# GSM_Communication_Signals.net
KiCad netlist of a schematic drawn in Altium Designer
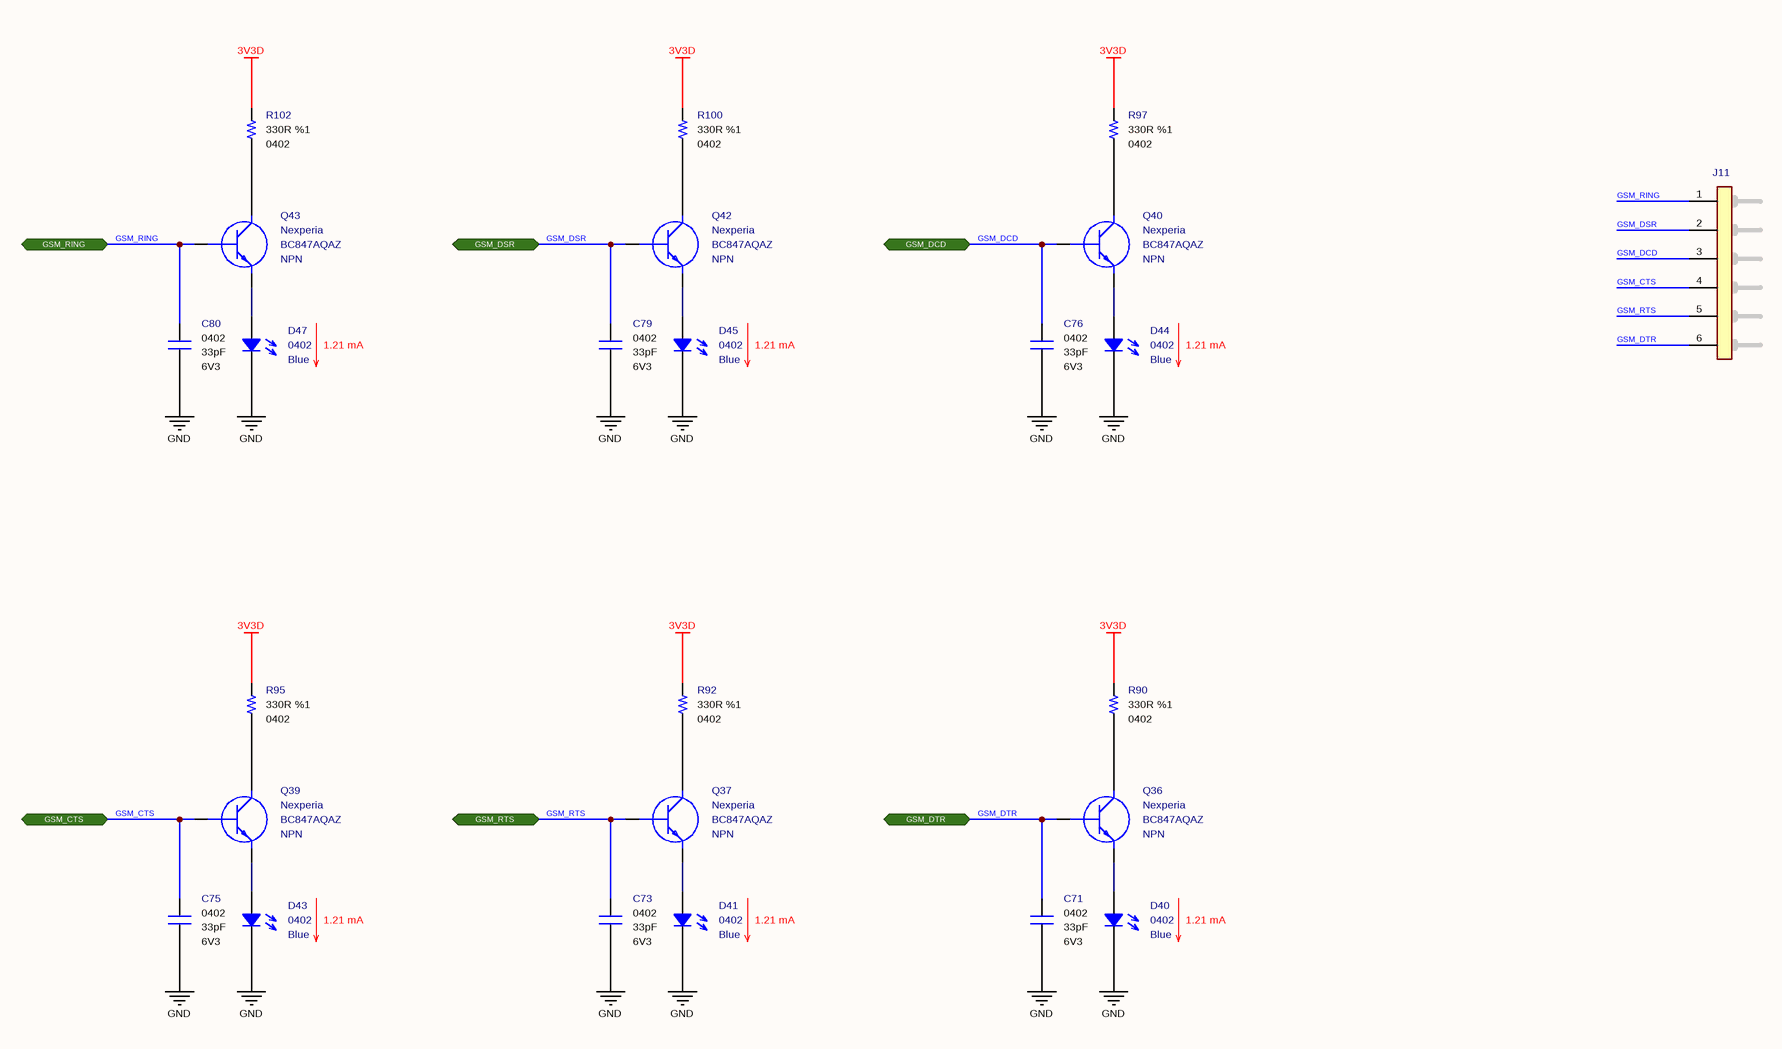
[diagram p0: GSM Communication Signals.SchDoc]

(export (version "E")
  (design (tool "Eeschema 10.0.6"))
  (components
    (comp (ref "C71")
      (value "33pF")
      (footprint "CAPACITOR_0402")
      (description "Capacitor - 33pF [0402] (Ceramic)")
      (fields
        (field (name "CASE") "0402")
        (field (name "TOLERANCE") "10%")
        (field (name "VOLTAGE") "6V3")
        (field (name "MANUFACTURER PART NUMBER") "C0402C330J9RACAUTO")
      )
      (libsource (lib "Ovoo_Library") (part "Capacitor - 33pF [0402-6V3]"))
    )
    (comp (ref "C73")
      (value "33pF")
      (footprint "CAPACITOR_0402")
      (description "Capacitor - 33pF [0402] (Ceramic)")
      (fields
        (field (name "CASE") "0402")
        (field (name "TOLERANCE") "10%")
        (field (name "VOLTAGE") "6V3")
        (field (name "MANUFACTURER PART NUMBER") "C0402C330J9RACAUTO")
      )
      (libsource (lib "Ovoo_Library") (part "Capacitor - 33pF [0402-6V3]"))
    )
    (comp (ref "C75")
      (value "33pF")
      (footprint "CAPACITOR_0402")
      (description "Capacitor - 33pF [0402] (Ceramic)")
      (fields
        (field (name "CASE") "0402")
        (field (name "TOLERANCE") "10%")
        (field (name "VOLTAGE") "6V3")
        (field (name "MANUFACTURER PART NUMBER") "C0402C330J9RACAUTO")
      )
      (libsource (lib "Ovoo_Library") (part "Capacitor - 33pF [0402-6V3]"))
    )
    (comp (ref "C76")
      (value "33pF")
      (footprint "CAPACITOR_0402")
      (description "Capacitor - 33pF [0402] (Ceramic)")
      (fields
        (field (name "CASE") "0402")
        (field (name "TOLERANCE") "10%")
        (field (name "VOLTAGE") "6V3")
        (field (name "MANUFACTURER PART NUMBER") "C0402C330J9RACAUTO")
      )
      (libsource (lib "Ovoo_Library") (part "Capacitor - 33pF [0402-6V3]"))
    )
    (comp (ref "C79")
      (value "33pF")
      (footprint "CAPACITOR_0402")
      (description "Capacitor - 33pF [0402] (Ceramic)")
      (fields
        (field (name "CASE") "0402")
        (field (name "TOLERANCE") "10%")
        (field (name "VOLTAGE") "6V3")
        (field (name "MANUFACTURER PART NUMBER") "C0402C330J9RACAUTO")
      )
      (libsource (lib "Ovoo_Library") (part "Capacitor - 33pF [0402-6V3]"))
    )
    (comp (ref "C80")
      (value "33pF")
      (footprint "CAPACITOR_0402")
      (description "Capacitor - 33pF [0402] (Ceramic)")
      (fields
        (field (name "CASE") "0402")
        (field (name "TOLERANCE") "10%")
        (field (name "VOLTAGE") "6V3")
        (field (name "MANUFACTURER PART NUMBER") "C0402C330J9RACAUTO")
      )
      (libsource (lib "Ovoo_Library") (part "Capacitor - 33pF [0402-6V3]"))
    )
    (comp (ref "D40")
      (value "SMD LED (Blue)")
      (footprint "LED_0402")
      (description "Standard LEDs - SMD PICOLEDTM;BLUE LED; 25M @ 5MA")
      (fields
        (field (name "MANUFACTURER_PART_NUMBER") "SMLP13BC8TT86")
        (field (name "MOUSER_PART_NUMBER") "755-SMLP13BC8TT86")
        (field (name "CASE") "0402")
        (field (name "COLOR") "Blue")
      )
      (libsource (lib "Ovoo_Library") (part "Diode - LED (0402-Blue)"))
    )
    (comp (ref "D41")
      (value "SMD LED (Blue)")
      (footprint "LED_0402")
      (description "Standard LEDs - SMD PICOLEDTM;BLUE LED; 25M @ 5MA")
      (fields
        (field (name "MANUFACTURER_PART_NUMBER") "SMLP13BC8TT86")
        (field (name "MOUSER_PART_NUMBER") "755-SMLP13BC8TT86")
        (field (name "CASE") "0402")
        (field (name "COLOR") "Blue")
      )
      (libsource (lib "Ovoo_Library") (part "Diode - LED (0402-Blue)"))
    )
    (comp (ref "D43")
      (value "SMD LED (Blue)")
      (footprint "LED_0402")
      (description "Standard LEDs - SMD PICOLEDTM;BLUE LED; 25M @ 5MA")
      (fields
        (field (name "MANUFACTURER_PART_NUMBER") "SMLP13BC8TT86")
        (field (name "MOUSER_PART_NUMBER") "755-SMLP13BC8TT86")
        (field (name "CASE") "0402")
        (field (name "COLOR") "Blue")
      )
      (libsource (lib "Ovoo_Library") (part "Diode - LED (0402-Blue)"))
    )
    (comp (ref "D44")
      (value "SMD LED (Blue)")
      (footprint "LED_0402")
      (description "Standard LEDs - SMD PICOLEDTM;BLUE LED; 25M @ 5MA")
      (fields
        (field (name "MANUFACTURER_PART_NUMBER") "SMLP13BC8TT86")
        (field (name "MOUSER_PART_NUMBER") "755-SMLP13BC8TT86")
        (field (name "CASE") "0402")
        (field (name "COLOR") "Blue")
      )
      (libsource (lib "Ovoo_Library") (part "Diode - LED (0402-Blue)"))
    )
    (comp (ref "D45")
      (value "SMD LED (Blue)")
      (footprint "LED_0402")
      (description "Standard LEDs - SMD PICOLEDTM;BLUE LED; 25M @ 5MA")
      (fields
        (field (name "MANUFACTURER_PART_NUMBER") "SMLP13BC8TT86")
        (field (name "MOUSER_PART_NUMBER") "755-SMLP13BC8TT86")
        (field (name "CASE") "0402")
        (field (name "COLOR") "Blue")
      )
      (libsource (lib "Ovoo_Library") (part "Diode - LED (0402-Blue)"))
    )
    (comp (ref "D47")
      (value "SMD LED (Blue)")
      (footprint "LED_0402")
      (description "Standard LEDs - SMD PICOLEDTM;BLUE LED; 25M @ 5MA")
      (fields
        (field (name "MANUFACTURER_PART_NUMBER") "SMLP13BC8TT86")
        (field (name "MOUSER_PART_NUMBER") "755-SMLP13BC8TT86")
        (field (name "CASE") "0402")
        (field (name "COLOR") "Blue")
      )
      (libsource (lib "Ovoo_Library") (part "Diode - LED (0402-Blue)"))
    )
    (comp (ref "J11")
      (value "2.54 mm Pitch 6P Male Connector")
      (footprint "6P Header")
      (description "Headers & Wire Housings BREAKAWAY HDR VERT 6")
      (fields
        (field (name "MANUFACTURER PART NUMBER") "22-28-4063")
        (field (name "MOUSER PART NUMBER") "538-22-28-4063")
      )
      (libsource (lib "Ovoo_Library") (part "Connector - Male Header 6P (2.54)"))
    )
    (comp (ref "Q36")
      (value "Bipolar NPN Transistors")
      (footprint "SOT1215")
      (description "Bipolar Transistors - BJT BC847AQA/DFN1010D-3/REEL 7\" Q2")
      (fields
        (field (name "MOUSER_PART_NUMBER") "771-BC847AQAZ")
        (field (name "MANUFACTURER_NAME") "Nexperia")
        (field (name "MANUFACTURER_PART_NUMBER") "BC847AQAZ")
        (field (name "POLARITY") "NPN")
      )
      (libsource (lib "Ovoo_Library") (part "Transistor - BC847"))
    )
    (comp (ref "Q37")
      (value "Bipolar NPN Transistors")
      (footprint "SOT1215")
      (description "Bipolar Transistors - BJT BC847AQA/DFN1010D-3/REEL 7\" Q2")
      (fields
        (field (name "MOUSER_PART_NUMBER") "771-BC847AQAZ")
        (field (name "MANUFACTURER_NAME") "Nexperia")
        (field (name "MANUFACTURER_PART_NUMBER") "BC847AQAZ")
        (field (name "POLARITY") "NPN")
      )
      (libsource (lib "Ovoo_Library") (part "Transistor - BC847"))
    )
    (comp (ref "Q39")
      (value "Bipolar NPN Transistors")
      (footprint "SOT1215")
      (description "Bipolar Transistors - BJT BC847AQA/DFN1010D-3/REEL 7\" Q2")
      (fields
        (field (name "MOUSER_PART_NUMBER") "771-BC847AQAZ")
        (field (name "MANUFACTURER_NAME") "Nexperia")
        (field (name "MANUFACTURER_PART_NUMBER") "BC847AQAZ")
        (field (name "POLARITY") "NPN")
      )
      (libsource (lib "Ovoo_Library") (part "Transistor - BC847"))
    )
    (comp (ref "Q40")
      (value "Bipolar NPN Transistors")
      (footprint "SOT1215")
      (description "Bipolar Transistors - BJT BC847AQA/DFN1010D-3/REEL 7\" Q2")
      (fields
        (field (name "MOUSER_PART_NUMBER") "771-BC847AQAZ")
        (field (name "MANUFACTURER_NAME") "Nexperia")
        (field (name "MANUFACTURER_PART_NUMBER") "BC847AQAZ")
        (field (name "POLARITY") "NPN")
      )
      (libsource (lib "Ovoo_Library") (part "Transistor - BC847"))
    )
    (comp (ref "Q42")
      (value "Bipolar NPN Transistors")
      (footprint "SOT1215")
      (description "Bipolar Transistors - BJT BC847AQA/DFN1010D-3/REEL 7\" Q2")
      (fields
        (field (name "MOUSER_PART_NUMBER") "771-BC847AQAZ")
        (field (name "MANUFACTURER_NAME") "Nexperia")
        (field (name "MANUFACTURER_PART_NUMBER") "BC847AQAZ")
        (field (name "POLARITY") "NPN")
      )
      (libsource (lib "Ovoo_Library") (part "Transistor - BC847"))
    )
    (comp (ref "Q43")
      (value "Bipolar NPN Transistors")
      (footprint "SOT1215")
      (description "Bipolar Transistors - BJT BC847AQA/DFN1010D-3/REEL 7\" Q2")
      (fields
        (field (name "MOUSER_PART_NUMBER") "771-BC847AQAZ")
        (field (name "MANUFACTURER_NAME") "Nexperia")
        (field (name "MANUFACTURER_PART_NUMBER") "BC847AQAZ")
        (field (name "POLARITY") "NPN")
      )
      (libsource (lib "Ovoo_Library") (part "Transistor - BC847"))
    )
    (comp (ref "R90")
      (value "330R")
      (footprint "RESISTOR_0402")
      (description "Thick Film Resistors - SMD 1/16 W 330 Ohm 1%")
      (fields
        (field (name "TOLERANCE") "%1")
        (field (name "CASE") "0402")
        (field (name "MANUFACTURER PART NUMBER") "CRCW0402330RFKED")
        (field (name "MOUSER PART NUMBER") "71-CRCW0402-330-E3")
      )
      (libsource (lib "Ovoo_Library") (part "Resistor - 330R"))
    )
    (comp (ref "R92")
      (value "330R")
      (footprint "RESISTOR_0402")
      (description "Thick Film Resistors - SMD 1/16 W 330 Ohm 1%")
      (fields
        (field (name "TOLERANCE") "%1")
        (field (name "CASE") "0402")
        (field (name "MANUFACTURER PART NUMBER") "CRCW0402330RFKED")
        (field (name "MOUSER PART NUMBER") "71-CRCW0402-330-E3")
      )
      (libsource (lib "Ovoo_Library") (part "Resistor - 330R"))
    )
    (comp (ref "R95")
      (value "330R")
      (footprint "RESISTOR_0402")
      (description "Thick Film Resistors - SMD 1/16 W 330 Ohm 1%")
      (fields
        (field (name "TOLERANCE") "%1")
        (field (name "CASE") "0402")
        (field (name "MANUFACTURER PART NUMBER") "CRCW0402330RFKED")
        (field (name "MOUSER PART NUMBER") "71-CRCW0402-330-E3")
      )
      (libsource (lib "Ovoo_Library") (part "Resistor - 330R"))
    )
    (comp (ref "R97")
      (value "330R")
      (footprint "RESISTOR_0402")
      (description "Thick Film Resistors - SMD 1/16 W 330 Ohm 1%")
      (fields
        (field (name "TOLERANCE") "%1")
        (field (name "CASE") "0402")
        (field (name "MANUFACTURER PART NUMBER") "CRCW0402330RFKED")
        (field (name "MOUSER PART NUMBER") "71-CRCW0402-330-E3")
      )
      (libsource (lib "Ovoo_Library") (part "Resistor - 330R"))
    )
    (comp (ref "R100")
      (value "330R")
      (footprint "RESISTOR_0402")
      (description "Thick Film Resistors - SMD 1/16 W 330 Ohm 1%")
      (fields
        (field (name "TOLERANCE") "%1")
        (field (name "CASE") "0402")
        (field (name "MANUFACTURER PART NUMBER") "CRCW0402330RFKED")
        (field (name "MOUSER PART NUMBER") "71-CRCW0402-330-E3")
      )
      (libsource (lib "Ovoo_Library") (part "Resistor - 330R"))
    )
    (comp (ref "R102")
      (value "330R")
      (footprint "RESISTOR_0402")
      (description "Thick Film Resistors - SMD 1/16 W 330 Ohm 1%")
      (fields
        (field (name "TOLERANCE") "%1")
        (field (name "CASE") "0402")
        (field (name "MANUFACTURER PART NUMBER") "CRCW0402330RFKED")
        (field (name "MOUSER PART NUMBER") "71-CRCW0402-330-E3")
      )
      (libsource (lib "Ovoo_Library") (part "Resistor - 330R"))
    )
  )
  (nets
    (net (code "1") (name "/GSM_CTS") (class "Default")
      (node (ref "C75") (pin "1") (pinfunction "1_1") (pintype "passive"))
      (node (ref "J11") (pin "4") (pinfunction "Pin-4_4") (pintype "passive"))
      (node (ref "Q39") (pin "1") (pinfunction "B_1") (pintype "passive"))
    )
    (net (code "2") (name "/GSM_DCD") (class "Default")
      (node (ref "C76") (pin "1") (pinfunction "1_1") (pintype "passive"))
      (node (ref "J11") (pin "3") (pinfunction "Pin-3_3") (pintype "passive"))
      (node (ref "Q40") (pin "1") (pinfunction "B_1") (pintype "passive"))
    )
    (net (code "3") (name "/GSM_DSR") (class "Default")
      (node (ref "C79") (pin "1") (pinfunction "1_1") (pintype "passive"))
      (node (ref "J11") (pin "2") (pinfunction "Pin-2_2") (pintype "passive"))
      (node (ref "Q42") (pin "1") (pinfunction "B_1") (pintype "passive"))
    )
    (net (code "4") (name "/GSM_DTR") (class "Default")
      (node (ref "C71") (pin "1") (pinfunction "1_1") (pintype "passive"))
      (node (ref "J11") (pin "6") (pinfunction "Pin-6_6") (pintype "passive"))
      (node (ref "Q36") (pin "1") (pinfunction "B_1") (pintype "passive"))
    )
    (net (code "5") (name "/GSM_RING") (class "Default")
      (node (ref "C80") (pin "1") (pinfunction "1_1") (pintype "passive"))
      (node (ref "J11") (pin "1") (pinfunction "Pin-1_1") (pintype "passive"))
      (node (ref "Q43") (pin "1") (pinfunction "B_1") (pintype "passive"))
    )
    (net (code "6") (name "/GSM_RTS") (class "Default")
      (node (ref "C73") (pin "1") (pinfunction "1_1") (pintype "passive"))
      (node (ref "J11") (pin "5") (pinfunction "Pin-5_5") (pintype "passive"))
      (node (ref "Q37") (pin "1") (pinfunction "B_1") (pintype "passive"))
    )
    (net (code "7") (name "3V3D") (class "Default")
      (node (ref "R100") (pin "2") (pinfunction "2_2") (pintype "passive"))
      (node (ref "R102") (pin "2") (pinfunction "2_2") (pintype "passive"))
      (node (ref "R90") (pin "2") (pinfunction "2_2") (pintype "passive"))
      (node (ref "R92") (pin "2") (pinfunction "2_2") (pintype "passive"))
      (node (ref "R95") (pin "2") (pinfunction "2_2") (pintype "passive"))
      (node (ref "R97") (pin "2") (pinfunction "2_2") (pintype "passive"))
    )
    (net (code "8") (name "GND") (class "Default")
      (node (ref "C71") (pin "2") (pinfunction "2_2") (pintype "passive"))
      (node (ref "C73") (pin "2") (pinfunction "2_2") (pintype "passive"))
      (node (ref "C75") (pin "2") (pinfunction "2_2") (pintype "passive"))
      (node (ref "C76") (pin "2") (pinfunction "2_2") (pintype "passive"))
      (node (ref "C79") (pin "2") (pinfunction "2_2") (pintype "passive"))
      (node (ref "C80") (pin "2") (pinfunction "2_2") (pintype "passive"))
      (node (ref "D40") (pin "1") (pinfunction "1_1") (pintype "passive"))
      (node (ref "D41") (pin "1") (pinfunction "1_1") (pintype "passive"))
      (node (ref "D43") (pin "1") (pinfunction "1_1") (pintype "passive"))
      (node (ref "D44") (pin "1") (pinfunction "1_1") (pintype "passive"))
      (node (ref "D45") (pin "1") (pinfunction "1_1") (pintype "passive"))
      (node (ref "D47") (pin "1") (pinfunction "1_1") (pintype "passive"))
    )
    (net (code "9") (name "Net-(Q36-C)") (class "Default")
      (node (ref "Q36") (pin "3") (pinfunction "C_3") (pintype "passive"))
      (node (ref "R90") (pin "1") (pinfunction "1_1") (pintype "passive"))
    )
    (net (code "10") (name "Net-(Q36-E)") (class "Default")
      (node (ref "D40") (pin "2") (pinfunction "2_2") (pintype "passive"))
      (node (ref "Q36") (pin "2") (pinfunction "E_2") (pintype "passive"))
    )
    (net (code "11") (name "Net-(Q37-C)") (class "Default")
      (node (ref "Q37") (pin "3") (pinfunction "C_3") (pintype "passive"))
      (node (ref "R92") (pin "1") (pinfunction "1_1") (pintype "passive"))
    )
    (net (code "12") (name "Net-(Q37-E)") (class "Default")
      (node (ref "D41") (pin "2") (pinfunction "2_2") (pintype "passive"))
      (node (ref "Q37") (pin "2") (pinfunction "E_2") (pintype "passive"))
    )
    (net (code "13") (name "Net-(Q39-C)") (class "Default")
      (node (ref "Q39") (pin "3") (pinfunction "C_3") (pintype "passive"))
      (node (ref "R95") (pin "1") (pinfunction "1_1") (pintype "passive"))
    )
    (net (code "14") (name "Net-(Q39-E)") (class "Default")
      (node (ref "D43") (pin "2") (pinfunction "2_2") (pintype "passive"))
      (node (ref "Q39") (pin "2") (pinfunction "E_2") (pintype "passive"))
    )
    (net (code "15") (name "Net-(Q40-C)") (class "Default")
      (node (ref "Q40") (pin "3") (pinfunction "C_3") (pintype "passive"))
      (node (ref "R97") (pin "1") (pinfunction "1_1") (pintype "passive"))
    )
    (net (code "16") (name "Net-(Q40-E)") (class "Default")
      (node (ref "D44") (pin "2") (pinfunction "2_2") (pintype "passive"))
      (node (ref "Q40") (pin "2") (pinfunction "E_2") (pintype "passive"))
    )
    (net (code "17") (name "Net-(Q42-C)") (class "Default")
      (node (ref "Q42") (pin "3") (pinfunction "C_3") (pintype "passive"))
      (node (ref "R100") (pin "1") (pinfunction "1_1") (pintype "passive"))
    )
    (net (code "18") (name "Net-(Q42-E)") (class "Default")
      (node (ref "D45") (pin "2") (pinfunction "2_2") (pintype "passive"))
      (node (ref "Q42") (pin "2") (pinfunction "E_2") (pintype "passive"))
    )
    (net (code "19") (name "Net-(Q43-C)") (class "Default")
      (node (ref "Q43") (pin "3") (pinfunction "C_3") (pintype "passive"))
      (node (ref "R102") (pin "1") (pinfunction "1_1") (pintype "passive"))
    )
    (net (code "20") (name "Net-(Q43-E)") (class "Default")
      (node (ref "D47") (pin "2") (pinfunction "2_2") (pintype "passive"))
      (node (ref "Q43") (pin "2") (pinfunction "E_2") (pintype "passive"))
    )
  )
)
